# det.net
KiCad netlist of a schematic drawn in Altium Designer
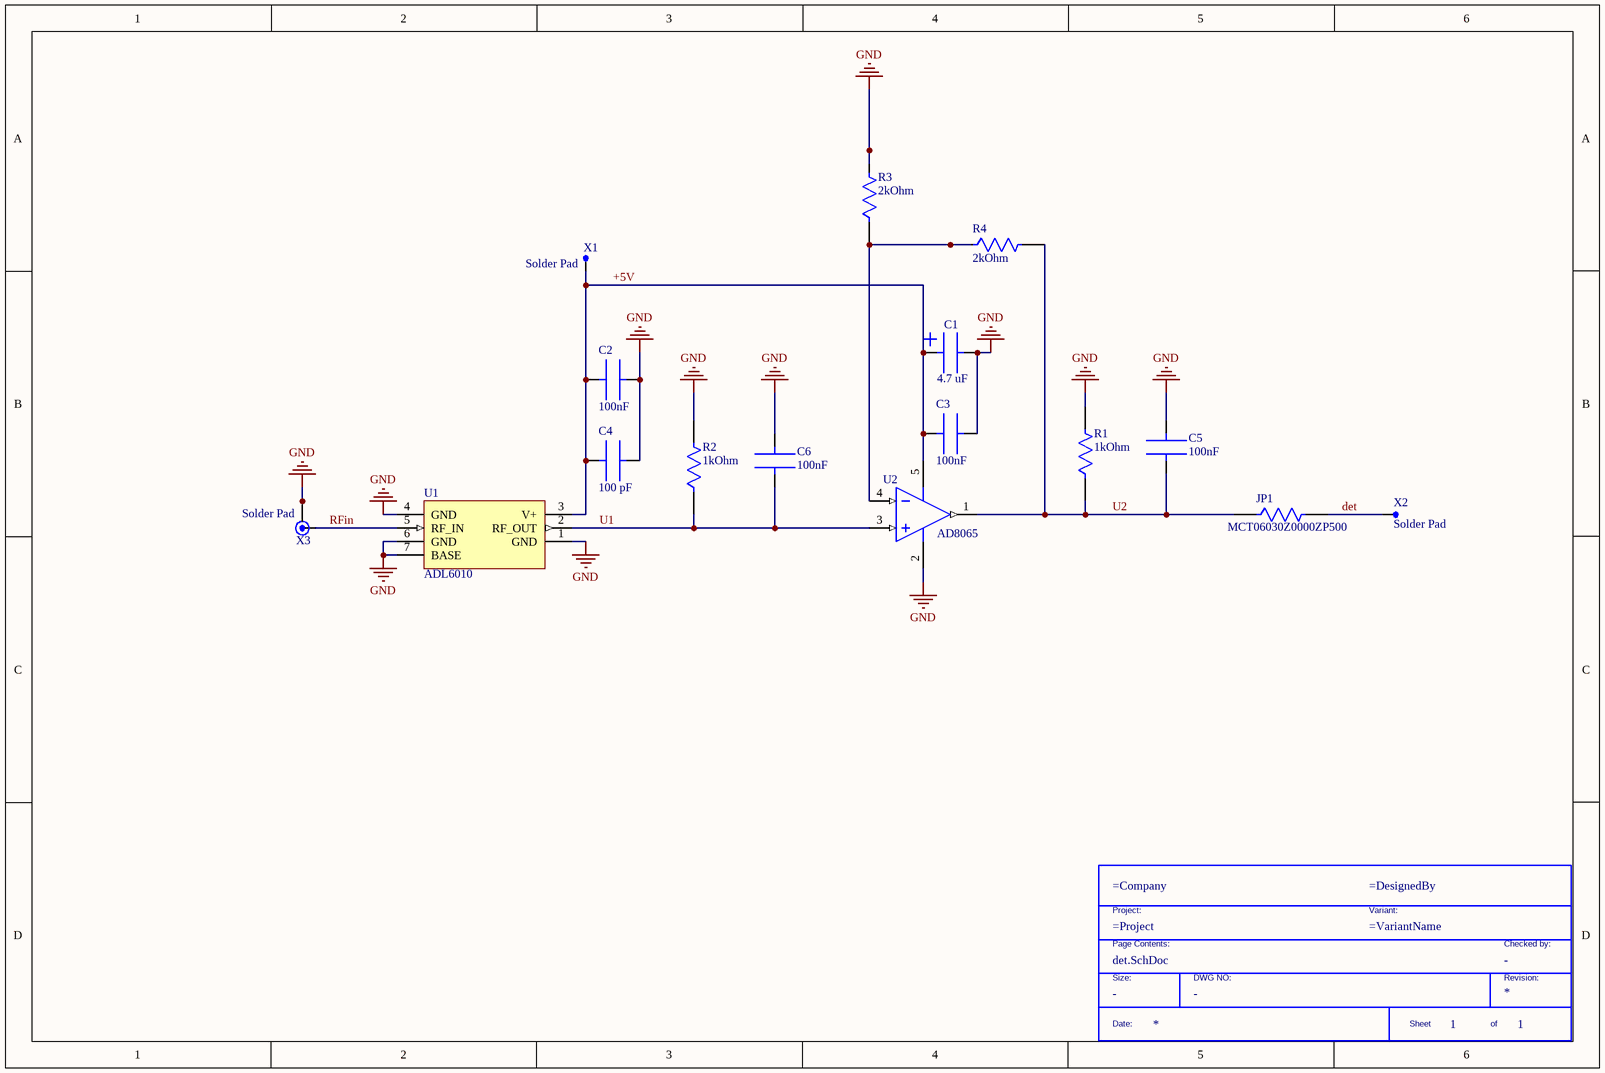
[diagram p0: det.SchDoc]

(export (version "E")
  (design (tool "Eeschema 10.0.6"))
  (components
    (comp (ref "*")
      (value "TitleBlock")
      (description "Standard Title Block")
      (fields (field (name "DWG NO") "-") (field (name "SIZE") "-") (field (name "CHECKED BY") "-"))
      (libsource (lib "amp") (part "TitleBlock"))
    )
    (comp (ref "C1")
      (value "4.7 uF")
      (footprint "C4_7uF")
      (fields
        (field (name "MANUFACTURER") "Vishay Sprague")
        (field (name "MANUFACTURER PART NUMBER") "TH3A475K010C2900")
      )
      (libsource (lib "det") (part "C7_4uF_TH3A475K010C2900"))
    )
    (comp (ref "C2")
      (value "100nF")
      (footprint "C1000pF__C100nF")
      (fields
        (field (name "MANUFACTURER") "Murata")
        (field (name "MANUFACTURER PART NUMBER") "GCM188R71C104KA37J")
      )
      (libsource (lib "det") (part "C100nF_GCM188R71C104KA37J"))
    )
    (comp (ref "C3")
      (value "100nF")
      (footprint "C1000pF__C100nF")
      (fields
        (field (name "MANUFACTURER") "Murata")
        (field (name "MANUFACTURER PART NUMBER") "GCM188R71C104KA37J")
      )
      (libsource (lib "det") (part "C100nF_GCM188R71C104KA37J"))
    )
    (comp (ref "C4")
      (value "100 pF")
      (footprint "C100pF")
      (description "Multilayer Ceramic Capacitors MLCC - SMD/SMT 100 pF 100 VDC 1% 0402 C0G (NP0)")
      (fields
        (field (name "MANUFACTURER") "Murata")
        (field (name "MANUFACTURER PART NUMBER") "GRM1555C2A101FA01D")
      )
      (libsource (lib "det") (part "C100pF_GRM1555C2A101FA01D"))
    )
    (comp (ref "C5")
      (value "100nF")
      (footprint "C1000pF__C100nF")
      (fields
        (field (name "MANUFACTURER") "Murata")
        (field (name "MANUFACTURER PART NUMBER") "GCM188R71C104KA37J")
      )
      (libsource (lib "det") (part "C100nF_GCM188R71C104KA37J"))
    )
    (comp (ref "C6")
      (value "100nF")
      (footprint "C1000pF__C100nF")
      (fields
        (field (name "MANUFACTURER") "Murata")
        (field (name "MANUFACTURER PART NUMBER") "GCM188R71C104KA37J")
      )
      (libsource (lib "det") (part "C100nF_GCM188R71C104KA37J"))
    )
    (comp (ref "JP1")
      (value "MCT06030Z0000ZP500")
      (footprint "JP_R_MCT06030Z0000ZP500")
      (description "Fixed Resistor, Thin Film, 0.1W, 0ohm, Surface Mount, 0603")
      (fields (field (name "MANUFACTURER") "Vishay Beyschlag") (field (name "POWER") "100mW"))
      (libsource (lib "det") (part "JP_small_MCT06030Z0000ZP500"))
    )
    (comp (ref "R1")
      (value "1kOhm")
      (footprint "JP_R_MCT06030Z0000ZP500")
      (description "Fixed Resistor, Thin Film, 0.1W, 1000ohm, 75V, 1% +/-Tol, 50ppm/Cel, Surface Mount, 0603")
      (fields
        (field (name "MANUFACTURER") "Vishay BCcomponents")
        (field (name "MANUFACTURER PART NUMBER") "MCT06030C1001FPW00")
      )
      (libsource (lib "det") (part "R_1kOhm_MCT06030C1001FPW00"))
    )
    (comp (ref "R2")
      (value "1kOhm")
      (footprint "JP_R_MCT06030Z0000ZP500")
      (description "Fixed Resistor, Thin Film, 0.1W, 1000ohm, 75V, 1% +/-Tol, 50ppm/Cel, Surface Mount, 0603")
      (fields
        (field (name "MANUFACTURER") "Vishay BCcomponents")
        (field (name "MANUFACTURER PART NUMBER") "MCT06030C1001FPW00")
      )
      (libsource (lib "det") (part "R_1kOhm_MCT06030C1001FPW00"))
    )
    (comp (ref "R3")
      (value "2kOhm")
      (footprint "JP_R_MCT06030Z0000ZP500")
      (description "Fixed Resistor, Thin Film, 0.1W, 1000ohm, 75V, 1% +/-Tol, 50ppm/Cel, Surface Mount, 0603")
      (fields
        (field (name "MANUFACTURER") "Vishay BCcomponents")
        (field (name "MANUFACTURER PART NUMBER") "MCT06030C1001FPW00")
      )
      (libsource (lib "det") (part "R_1kOhm_MCT06030C1001FPW00"))
    )
    (comp (ref "R4")
      (value "2kOhm")
      (footprint "JP_R_MCT06030Z0000ZP500")
      (description "Fixed Resistor, Thin Film, 0.1W, 1000ohm, 75V, 1% +/-Tol, 50ppm/Cel, Surface Mount, 0603")
      (fields
        (field (name "MANUFACTURER") "Vishay BCcomponents")
        (field (name "MANUFACTURER PART NUMBER") "MCT06030C1001FPW00")
      )
      (libsource (lib "det") (part "R_1kOhm_MCT06030C1001FPW00"))
    )
    (comp (ref "U1")
      (value "ADL6010")
      (footprint "Det_ADL6010ACPZN-R2")
      (description "Linear Detector, 500MHz Min, 43500MHz Max, 20dBm Input Power-Max")
      (fields
        (field (name "MANUFACTURER") "Analog Devices")
        (field (name "MANUFACTURER PART NUMBER") "ADL6010ACPZN-R2")
      )
      (libsource (lib "det") (part "det_ADL6010ACPZN-R2"))
    )
    (comp (ref "U2")
      (value "AD8065")
      (footprint "opAmp_AD8065ARTZ-REEL7")
      (description "Operational Amplifier, 1 Func, BIPolar, PDSO5")
      (fields
        (field (name "MANUFACTURER") "Analog Devices")
        (field (name "MANUFACTURER PART NUMBER") "AD8065ARTZ-REEL7")
      )
      (libsource (lib "det") (part "opAmp_AD8065ARTZ-REEL7"))
    )
    (comp (ref "X1")
      (value "Solder Pad")
      (footprint "Solder Pad")
      (description "Pad to solder wires to")
      (libsource (lib "det") (part "Solder Pad"))
    )
    (comp (ref "X2")
      (value "Solder Pad")
      (footprint "Solder Pad")
      (description "Pad to solder wires to")
      (libsource (lib "det") (part "Solder Pad"))
    )
    (comp (ref "X3")
      (value "Solder Pad")
      (footprint "CPW Edge Connector")
      (description "Solder pad for RF Coplanar Waveguide Rogers 4350B Thickness 0.020\" Copper 1oz")
      (libsource (lib "det") (part "RF  CPW Solder Pad"))
    )
  )
  (nets
    (net (code "1") (name "/+5V") (class "Default")
      (node (ref "C1") (pin "1") (pinfunction "+_1") (pintype "passive"))
      (node (ref "C2") (pin "1") (pinfunction "1_1") (pintype "passive"))
      (node (ref "C3") (pin "1") (pinfunction "1_1") (pintype "passive"))
      (node (ref "C4") (pin "1") (pinfunction "1_1") (pintype "passive"))
      (node (ref "U1") (pin "3") (pinfunction "V+_3") (pintype "passive"))
      (node (ref "U2") (pin "5") (pinfunction "+VS_5") (pintype "power_in"))
      (node (ref "X1") (pin "1") (pinfunction "1_1") (pintype "passive"))
    )
    (net (code "2") (name "/RFin") (class "Default")
      (node (ref "U1") (pin "5") (pinfunction "RF_IN_5") (pintype "input"))
      (node (ref "X3") (pin "1") (pinfunction "1_1") (pintype "passive"))
    )
    (net (code "3") (name "/U1") (class "Default")
      (node (ref "C6") (pin "1") (pinfunction "1_1") (pintype "passive"))
      (node (ref "R2") (pin "1") (pinfunction "1_1") (pintype "passive"))
      (node (ref "U1") (pin "2") (pinfunction "RF_OUT_2") (pintype "output"))
      (node (ref "U2") (pin "3") (pinfunction "+IN_3") (pintype "input"))
    )
    (net (code "4") (name "/U2") (class "Default")
      (node (ref "C5") (pin "1") (pinfunction "1_1") (pintype "passive"))
      (node (ref "JP1") (pin "1") (pinfunction "1_1") (pintype "passive"))
      (node (ref "R1") (pin "1") (pinfunction "1_1") (pintype "passive"))
      (node (ref "R4") (pin "2") (pinfunction "2_2") (pintype "passive"))
      (node (ref "U2") (pin "1") (pinfunction "VOUT_1") (pintype "output"))
    )
    (net (code "5") (name "/det") (class "Default")
      (node (ref "JP1") (pin "2") (pinfunction "2_2") (pintype "passive"))
      (node (ref "X2") (pin "1") (pinfunction "1_1") (pintype "passive"))
    )
    (net (code "6") (name "GND") (class "Default")
      (node (ref "C1") (pin "2") (pinfunction "2_2") (pintype "passive"))
      (node (ref "C2") (pin "2") (pinfunction "2_2") (pintype "passive"))
      (node (ref "C3") (pin "2") (pinfunction "2_2") (pintype "passive"))
      (node (ref "C4") (pin "2") (pinfunction "2_2") (pintype "passive"))
      (node (ref "C5") (pin "2") (pinfunction "2_2") (pintype "passive"))
      (node (ref "C6") (pin "2") (pinfunction "2_2") (pintype "passive"))
      (node (ref "R1") (pin "2") (pinfunction "2_2") (pintype "passive"))
      (node (ref "R2") (pin "2") (pinfunction "2_2") (pintype "passive"))
      (node (ref "R3") (pin "2") (pinfunction "2_2") (pintype "passive"))
      (node (ref "U1") (pin "1") (pinfunction "GND_1") (pintype "passive"))
      (node (ref "U1") (pin "4") (pinfunction "GND_4") (pintype "passive"))
      (node (ref "U1") (pin "6") (pinfunction "GND_6") (pintype "passive"))
      (node (ref "U1") (pin "7") (pinfunction "BASE_7") (pintype "passive"))
      (node (ref "U2") (pin "2") (pinfunction "-VS_2") (pintype "power_in"))
      (node (ref "X3") (pin "2") (pinfunction "2_2") (pintype "passive"))
      (node (ref "X3") (pin "3") (pinfunction "3_3") (pintype "passive"))
    )
    (net (code "7") (name "Net-(U2--IN)") (class "Default")
      (node (ref "R3") (pin "1") (pinfunction "1_1") (pintype "passive"))
      (node (ref "R4") (pin "1") (pinfunction "1_1") (pintype "passive"))
      (node (ref "U2") (pin "4") (pinfunction "-IN_4") (pintype "input"))
    )
  )
)
